# white_noise.net
KiCad netlist of a schematic drawn in Altium Designer
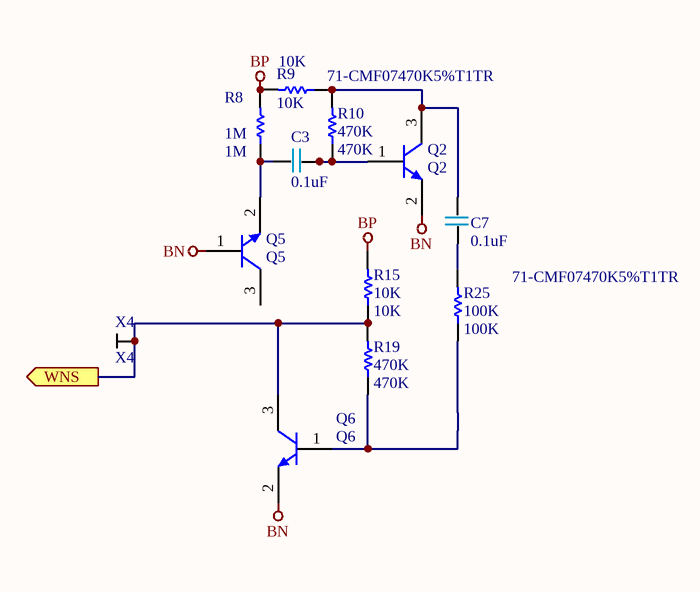
[diagram p0: white_noise.SchDoc]

(export (version "E")
  (design (tool "Eeschema 10.0.6"))
  (components
    (comp (ref "C3")
      (value "0.1uF")
      (footprint "Cap Film 5")
      (libsource (lib "MyLibrary") (part "Cap Film 5"))
    )
    (comp (ref "C7")
      (value "0.1uF")
      (footprint "Cap Film 5")
      (libsource (lib "MyLibrary") (part "Cap Film 5"))
    )
    (comp (ref "Q2")
      (value "Q2")
      (footprint "ONSC-SC-75-3-463-01_V")
      (description "General Purpose Transistor, NPN Silicon, 3-Pin SC-75, Pb-Free, Tape and Reel")
      (fields (field (name "MANUFACTURER") "On Semiconductor") (field (name "PARTNUMBER") "MMBT3904TT1G"))
      (libsource (lib "ON Semi General Purpose Transistors") (part "MMBT3904TT1G"))
    )
    (comp (ref "Q5")
      (value "Q5")
      (footprint "ONSC-SC-75-3-463-01_V")
      (description "General Purpose Transistor, NPN Silicon, 3-Pin SC-75, Pb-Free, Tape and Reel")
      (fields (field (name "MANUFACTURER") "On Semiconductor") (field (name "PARTNUMBER") "MMBT3904TT1G"))
      (libsource (lib "ON Semi General Purpose Transistors") (part "MMBT3904TT1G"))
    )
    (comp (ref "Q6")
      (value "Q6")
      (footprint "ONSC-SC-75-3-463-01_V")
      (description "General Purpose Transistor, NPN Silicon, 3-Pin SC-75, Pb-Free, Tape and Reel")
      (fields (field (name "MANUFACTURER") "On Semiconductor") (field (name "PARTNUMBER") "MMBT3904TT1G"))
      (libsource (lib "ON Semi General Purpose Transistors") (part "MMBT3904TT1G"))
    )
    (comp (ref "R8")
      (value "1M")
      (footprint "AXIAL-0.3")
      (description "Resistor")
      (fields
        (field (name "ALTIUM_VALUE") "1M")
        (field (name "MANUFACTURER") "Vishay / Dale")
        (field (name "MANUFACTURER PART NUMBER") "CMF551M0000FKEB")
        (field (name "PUBLISHER") "Altium Limited")
      )
      (libsource (lib "Miscellaneous Devices") (part "Res1"))
    )
    (comp (ref "R9")
      (value "10K")
      (footprint "AXIAL-0.3")
      (description "Resistor")
      (fields
        (field (name "ALTIUM_VALUE") "10K")
        (field (name "MANUFACTURER PART NUMBER") "CCF0710K0JKE36")
        (field (name "PUBLISHER") "Altium Limited")
      )
      (libsource (lib "Miscellaneous Devices") (part "Res1"))
    )
    (comp (ref "R10")
      (value "470K")
      (footprint "AXIAL-0.3")
      (description "Resistor")
      (fields
        (field (name "ALTIUM_VALUE") "470K")
        (field (name "SUPPLIER PART NUMBER 1") "71-CMF07470K5%T1TR")
        (field (name "MANUFACTURER") "Vishay / Dale")
        (field (name "MANUFACTURER PART NUMBER") "CMF07470K00JKR6")
        (field (name "PUBLISHER") "Altium Limited")
      )
      (libsource (lib "Miscellaneous Devices") (part "Res1"))
    )
    (comp (ref "R15")
      (value "10K")
      (footprint "AXIAL-0.3")
      (description "Resistor")
      (fields
        (field (name "ALTIUM_VALUE") "10K")
        (field (name "MANUFACTURER PART NUMBER") "CCF0710K0JKE36")
        (field (name "PUBLISHER") "Altium Limited")
      )
      (libsource (lib "Miscellaneous Devices") (part "Res1"))
    )
    (comp (ref "R19")
      (value "470K")
      (footprint "AXIAL-0.3")
      (description "Resistor")
      (fields
        (field (name "ALTIUM_VALUE") "470K")
        (field (name "SUPPLIER PART NUMBER 1") "71-CMF07470K5%T1TR")
        (field (name "MANUFACTURER") "Vishay / Dale")
        (field (name "MANUFACTURER PART NUMBER") "CMF07470K00JKR6")
        (field (name "PUBLISHER") "Altium Limited")
      )
      (libsource (lib "Miscellaneous Devices") (part "Res1"))
    )
    (comp (ref "R25")
      (value "100K")
      (footprint "AXIAL-0.3")
      (description "Resistor")
      (fields
        (field (name "ALTIUM_VALUE") "100K")
        (field (name "MANUFACTURER") "Vishay / Dale")
        (field (name "MANUFACTURER PART NUMBER") "CMF55100K00FHEK")
        (field (name "PUBLISHER") "Altium Limited")
      )
      (libsource (lib "Miscellaneous Devices") (part "Res1"))
    )
    (comp (ref "X4") (value "X4") (footprint "Pad") (libsource (lib "MyLibrary") (part "Pad")))
  )
  (nets
    (net (code "1") (name "/WNS") (class "Default")
      (node (ref "Q6") (pin "3") (pinfunction "C_3") (pintype "passive"))
      (node (ref "R15") (pin "1") (pinfunction "1_1") (pintype "passive"))
      (node (ref "R19") (pin "2") (pinfunction "2_2") (pintype "passive"))
      (node (ref "X4") (pin "1") (pinfunction "1_1") (pintype "passive"))
    )
    (net (code "2") (name "BN") (class "Default")
      (node (ref "Q2") (pin "2") (pinfunction "E_2") (pintype "passive"))
      (node (ref "Q5") (pin "1") (pinfunction "B_1") (pintype "passive"))
      (node (ref "Q6") (pin "2") (pinfunction "E_2") (pintype "passive"))
    )
    (net (code "3") (name "BP") (class "Default")
      (node (ref "R15") (pin "2") (pinfunction "2_2") (pintype "passive"))
      (node (ref "R8") (pin "2") (pinfunction "2_2") (pintype "passive"))
      (node (ref "R9") (pin "2") (pinfunction "2_2") (pintype "passive"))
    )
    (net (code "4") (name "Net-(C7-Pad1)") (class "Default")
      (node (ref "C7") (pin "1") (pinfunction "1_1") (pintype "passive"))
      (node (ref "R25") (pin "2") (pinfunction "2_2") (pintype "passive"))
    )
    (net (code "5") (name "Net-(Q2-B)") (class "Default")
      (node (ref "C3") (pin "2") (pinfunction "2_2") (pintype "passive"))
      (node (ref "Q2") (pin "1") (pinfunction "B_1") (pintype "passive"))
      (node (ref "R10") (pin "1") (pinfunction "1_1") (pintype "passive"))
    )
    (net (code "6") (name "Net-(Q2-C)") (class "Default")
      (node (ref "C7") (pin "2") (pinfunction "2_2") (pintype "passive"))
      (node (ref "Q2") (pin "3") (pinfunction "C_3") (pintype "passive"))
      (node (ref "R10") (pin "2") (pinfunction "2_2") (pintype "passive"))
      (node (ref "R9") (pin "1") (pinfunction "1_1") (pintype "passive"))
    )
    (net (code "7") (name "Net-(Q5-E)") (class "Default")
      (node (ref "C3") (pin "1") (pinfunction "1_1") (pintype "passive"))
      (node (ref "Q5") (pin "2") (pinfunction "E_2") (pintype "passive"))
      (node (ref "R8") (pin "1") (pinfunction "1_1") (pintype "passive"))
    )
    (net (code "8") (name "Net-(Q6-B)") (class "Default")
      (node (ref "Q6") (pin "1") (pinfunction "B_1") (pintype "passive"))
      (node (ref "R19") (pin "1") (pinfunction "1_1") (pintype "passive"))
      (node (ref "R25") (pin "1") (pinfunction "1_1") (pintype "passive"))
    )
    (net (code "9") (name "unconnected-(Q5-C-Pad3)") (class "Default")
      (node (ref "Q5") (pin "3") (pinfunction "C_3") (pintype "passive"))
    )
  )
)
